# SOM_JB2.net
KiCad netlist of a schematic drawn in Altium Designer
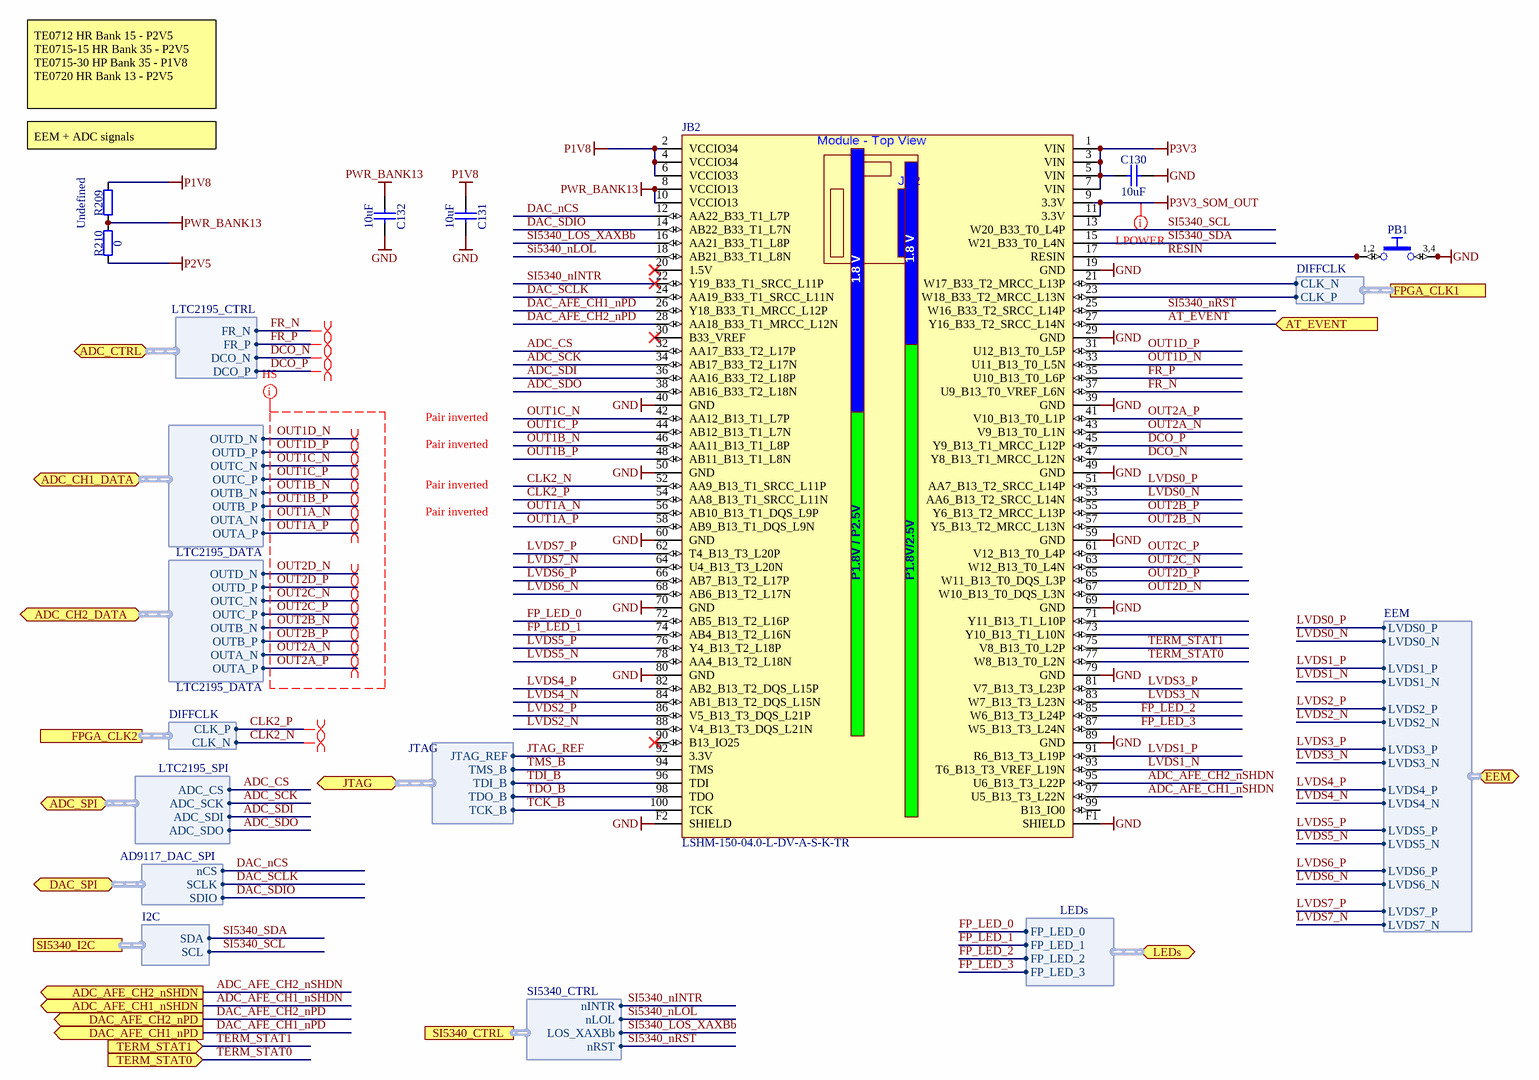
[diagram p0: SOM_JB2.SchDoc]

(export (version "E")
  (design (tool "Eeschema 10.0.6"))
  (components
    (comp (ref "C130")
      (value "10uF")
      (footprint "CAPC1608X80N")
      (description "Non-polarised capacitor")
      (fields
        (field (name "PART NUMBER") "CC0603_10UF_10V_10%_X5R")
        (field (name "VOLTAGE") "10V")
        (field (name "AUTHOR") "CERN DEM JLC")
      )
      (libsource (lib "Capacitors") (part "Capacitor - non polarized"))
    )
    (comp (ref "C131")
      (value "10uF")
      (footprint "CAPC1608X80N")
      (description "Non-polarised capacitor")
      (fields
        (field (name "PART NUMBER") "CC0603_10UF_10V_10%_X5R")
        (field (name "VOLTAGE") "10V")
        (field (name "AUTHOR") "CERN DEM JLC")
      )
      (libsource (lib "Capacitors") (part "Capacitor - non polarized"))
    )
    (comp (ref "C132")
      (value "10uF")
      (footprint "CAPC1608X80N")
      (description "Non-polarised capacitor")
      (fields
        (field (name "PART NUMBER") "CC0603_10UF_10V_10%_X5R")
        (field (name "VOLTAGE") "10V")
        (field (name "AUTHOR") "CERN DEM JLC")
      )
      (libsource (lib "Capacitors") (part "Capacitor - non polarized"))
    )
    (comp (ref "JB2")
      (value "LSHM-150-04.0-L-DV-A-S-K-TR")
      (footprint "LSHM-150-XXX-X-DV-A-X")
      (description "Samtec Razor Beam REF-189017-02, LF-04.0, 60 Pins, für alle 4x5 SoMs")
      (libsource (lib "SVPX_FMC_6U_SOM") (part "25286"))
    )
    (comp (ref "PB1")
      (value "Push Button")
      (footprint "PB_TYCO_FSM6JSMA")
      (description "Push-Button Switch SPDT")
      (fields
        (field (name "PART NUMBER") "PB_TYCO_FSM6JSMA")
        (field (name "MANUFACTURER") "TYCO ELECTRONICS")
        (field (name "AUTHOR") "CERN DEM JLC")
      )
      (libsource (lib "Eletro-mechanical") (part "PB SPST 12NO-34NO"))
    )
    (comp (ref "R209")
      (value "Undefined")
      (footprint "RESC1608X55N")
      (description "Resistor")
      (fields (field (name "PART NUMBER") "R0603_NO-VALUE") (field (name "AUTHOR") "CERN DEM JLC"))
      (libsource (lib "Resistors") (part "Resistor"))
    )
    (comp (ref "R210")
      (value "0")
      (footprint "RESC1005X40N")
      (description "Resistor")
      (fields
        (field (name "PART NUMBER") "R0402_0R_JUMPER")
        (field (name "MANUFACTURER") "GENERIC")
        (field (name "AUTHOR") "CERN DEM JLC")
      )
      (libsource (lib "Resistors") (part "Resistor"))
    )
  )
  (nets
    (net (code "11") (name "/ADC_AFE_CH1_nSHDN") (class "Default")
      (node (ref "JB2") (pin "97") (pinfunction "U5_B13_T3_L22N_97") (pintype "bidirectional"))
    )
    (net (code "12") (name "/ADC_AFE_CH2_nSHDN") (class "Default")
      (node (ref "JB2") (pin "95") (pinfunction "U6_B13_T3_L22P_95") (pintype "bidirectional"))
    )
    (net (code "13") (name "/ADC_CS") (class "Default")
      (node (ref "JB2") (pin "32") (pinfunction "AA17_B33_T2_L17P_32") (pintype "bidirectional"))
    )
    (net (code "14") (name "/ADC_SCK") (class "Default")
      (node (ref "JB2") (pin "34") (pinfunction "AB17_B33_T2_L17N_34") (pintype "bidirectional"))
    )
    (net (code "15") (name "/ADC_SDI") (class "Default")
      (node (ref "JB2") (pin "36") (pinfunction "AA16_B33_T2_L18P_36") (pintype "bidirectional"))
    )
    (net (code "16") (name "/ADC_SDO") (class "Default")
      (node (ref "JB2") (pin "38") (pinfunction "AB16_B33_T2_L18N_38") (pintype "bidirectional"))
    )
    (net (code "17") (name "/AT_EVENT") (class "Default")
      (node (ref "JB2") (pin "27") (pinfunction "Y16_B33_T2_SRCC_L14N_27") (pintype "bidirectional"))
    )
    (net (code "18") (name "/CLK2_N") (class "Default")
      (node (ref "JB2") (pin "52") (pinfunction "AA9_B13_T1_SRCC_L11P_52") (pintype "bidirectional"))
    )
    (net (code "19") (name "/CLK2_P") (class "Default")
      (node (ref "JB2") (pin "54") (pinfunction "AA8_B13_T1_SRCC_L11N_54") (pintype "bidirectional"))
    )
    (net (code "20") (name "/DAC_AFE_CH1_nPD") (class "Default")
      (node (ref "JB2") (pin "26") (pinfunction "Y18_B33_T1_MRCC_L12P_26") (pintype "bidirectional"))
    )
    (net (code "21") (name "/DAC_AFE_CH2_nPD") (class "Default")
      (node (ref "JB2") (pin "28") (pinfunction "AA18_B33_T1_MRCC_L12N_28") (pintype "bidirectional"))
    )
    (net (code "22") (name "/DAC_SCLK") (class "Default")
      (node (ref "JB2") (pin "24") (pinfunction "AA19_B33_T1_SRCC_L11N_24") (pintype "bidirectional"))
    )
    (net (code "23") (name "/DAC_SDIO") (class "Default")
      (node (ref "JB2") (pin "14") (pinfunction "AB22_B33_T1_L7N_14") (pintype "bidirectional"))
    )
    (net (code "24") (name "/DAC_nCS") (class "Default")
      (node (ref "JB2") (pin "12") (pinfunction "AA22_B33_T1_L7P_12") (pintype "bidirectional"))
    )
    (net (code "25") (name "/DCO_N") (class "Default")
      (node (ref "JB2") (pin "47") (pinfunction "Y8_B13_T1_MRCC_L12N_47") (pintype "bidirectional"))
    )
    (net (code "26") (name "/DCO_P") (class "Default")
      (node (ref "JB2") (pin "45") (pinfunction "Y9_B13_T1_MRCC_L12P_45") (pintype "bidirectional"))
    )
    (net (code "27") (name "/FP_LED_0") (class "Default")
      (node (ref "JB2") (pin "72") (pinfunction "AB5_B13_T2_L16P_72") (pintype "bidirectional"))
    )
    (net (code "28") (name "/FP_LED_1") (class "Default")
      (node (ref "JB2") (pin "74") (pinfunction "AB4_B13_T2_L16N_74") (pintype "bidirectional"))
    )
    (net (code "29") (name "/FP_LED_2") (class "Default")
      (node (ref "JB2") (pin "85") (pinfunction "W6_B13_T3_L24P_85") (pintype "bidirectional"))
    )
    (net (code "30") (name "/FP_LED_3") (class "Default")
      (node (ref "JB2") (pin "87") (pinfunction "W5_B13_T3_L24N_87") (pintype "bidirectional"))
    )
    (net (code "31") (name "/FR_N") (class "Default")
      (node (ref "JB2") (pin "37") (pinfunction "U9_B13_T0_VREF_L6N_37") (pintype "bidirectional"))
    )
    (net (code "32") (name "/FR_P") (class "Default")
      (node (ref "JB2") (pin "35") (pinfunction "U10_B13_T0_L6P_35") (pintype "bidirectional"))
    )
    (net (code "33") (name "/JTAG_REF") (class "Default")
      (node (ref "JB2") (pin "92") (pinfunction "3.3V_92") (pintype "power_in"))
    )
    (net (code "34") (name "/LVDS0_N") (class "Default")
      (node (ref "JB2") (pin "53") (pinfunction "AA6_B13_T2_SRCC_L14N_53") (pintype "bidirectional"))
    )
    (net (code "35") (name "/LVDS0_P") (class "Default")
      (node (ref "JB2") (pin "51") (pinfunction "AA7_B13_T2_SRCC_L14P_51") (pintype "bidirectional"))
    )
    (net (code "36") (name "/LVDS1_N") (class "Default")
      (node (ref "JB2") (pin "93") (pinfunction "T6_B13_T3_VREF_L19N_93") (pintype "bidirectional"))
    )
    (net (code "37") (name "/LVDS1_P") (class "Default")
      (node (ref "JB2") (pin "91") (pinfunction "R6_B13_T3_L19P_91") (pintype "bidirectional"))
    )
    (net (code "38") (name "/LVDS2_N") (class "Default")
      (node (ref "JB2") (pin "88") (pinfunction "V4_B13_T3_DQS_L21N_88") (pintype "bidirectional"))
    )
    (net (code "39") (name "/LVDS2_P") (class "Default")
      (node (ref "JB2") (pin "86") (pinfunction "V5_B13_T3_DQS_L21P_86") (pintype "bidirectional"))
    )
    (net (code "40") (name "/LVDS3_N") (class "Default")
      (node (ref "JB2") (pin "83") (pinfunction "W7_B13_T3_L23N_83") (pintype "bidirectional"))
    )
    (net (code "41") (name "/LVDS3_P") (class "Default")
      (node (ref "JB2") (pin "81") (pinfunction "V7_B13_T3_L23P_81") (pintype "bidirectional"))
    )
    (net (code "42") (name "/LVDS4_N") (class "Default")
      (node (ref "JB2") (pin "84") (pinfunction "AB1_B13_T2_DQS_L15N_84") (pintype "bidirectional"))
    )
    (net (code "43") (name "/LVDS4_P") (class "Default")
      (node (ref "JB2") (pin "82") (pinfunction "AB2_B13_T2_DQS_L15P_82") (pintype "bidirectional"))
    )
    (net (code "44") (name "/LVDS5_N") (class "Default")
      (node (ref "JB2") (pin "78") (pinfunction "AA4_B13_T2_L18N_78") (pintype "bidirectional"))
    )
    (net (code "45") (name "/LVDS5_P") (class "Default")
      (node (ref "JB2") (pin "76") (pinfunction "Y4_B13_T2_L18P_76") (pintype "bidirectional"))
    )
    (net (code "46") (name "/LVDS6_N") (class "Default")
      (node (ref "JB2") (pin "68") (pinfunction "AB6_B13_T2_L17N_68") (pintype "bidirectional"))
    )
    (net (code "47") (name "/LVDS6_P") (class "Default")
      (node (ref "JB2") (pin "66") (pinfunction "AB7_B13_T2_L17P_66") (pintype "bidirectional"))
    )
    (net (code "48") (name "/LVDS7_N") (class "Default")
      (node (ref "JB2") (pin "64") (pinfunction "U4_B13_T3_L20N_64") (pintype "bidirectional"))
    )
    (net (code "49") (name "/LVDS7_P") (class "Default")
      (node (ref "JB2") (pin "62") (pinfunction "T4_B13_T3_L20P_62") (pintype "bidirectional"))
    )
    (net (code "50") (name "/OUT1A_N") (class "Default")
      (node (ref "JB2") (pin "56") (pinfunction "AB10_B13_T1_DQS_L9P_56") (pintype "bidirectional"))
    )
    (net (code "51") (name "/OUT1A_P") (class "Default")
      (node (ref "JB2") (pin "58") (pinfunction "AB9_B13_T1_DQS_L9N_58") (pintype "bidirectional"))
    )
    (net (code "52") (name "/OUT1B_N") (class "Default")
      (node (ref "JB2") (pin "46") (pinfunction "AA11_B13_T1_L8P_46") (pintype "bidirectional"))
    )
    (net (code "53") (name "/OUT1B_P") (class "Default")
      (node (ref "JB2") (pin "48") (pinfunction "AB11_B13_T1_L8N_48") (pintype "bidirectional"))
    )
    (net (code "54") (name "/OUT1C_N") (class "Default")
      (node (ref "JB2") (pin "42") (pinfunction "AA12_B13_T1_L7P_42") (pintype "bidirectional"))
    )
    (net (code "55") (name "/OUT1C_P") (class "Default")
      (node (ref "JB2") (pin "44") (pinfunction "AB12_B13_T1_L7N_44") (pintype "bidirectional"))
    )
    (net (code "56") (name "/OUT1D_N") (class "Default")
      (node (ref "JB2") (pin "33") (pinfunction "U11_B13_T0_L5N_33") (pintype "bidirectional"))
    )
    (net (code "57") (name "/OUT1D_P") (class "Default")
      (node (ref "JB2") (pin "31") (pinfunction "U12_B13_T0_L5P_31") (pintype "bidirectional"))
    )
    (net (code "58") (name "/OUT2A_N") (class "Default")
      (node (ref "JB2") (pin "43") (pinfunction "V9_B13_T0_L1N_43") (pintype "bidirectional"))
    )
    (net (code "59") (name "/OUT2A_P") (class "Default")
      (node (ref "JB2") (pin "41") (pinfunction "V10_B13_T0_L1P_41") (pintype "bidirectional"))
    )
    (net (code "60") (name "/OUT2B_N") (class "Default")
      (node (ref "JB2") (pin "57") (pinfunction "Y5_B13_T2_MRCC_L13N_57") (pintype "bidirectional"))
    )
    (net (code "61") (name "/OUT2B_P") (class "Default")
      (node (ref "JB2") (pin "55") (pinfunction "Y6_B13_T2_MRCC_L13P_55") (pintype "bidirectional"))
    )
    (net (code "62") (name "/OUT2C_N") (class "Default")
      (node (ref "JB2") (pin "63") (pinfunction "W12_B13_T0_L4N_63") (pintype "bidirectional"))
    )
    (net (code "63") (name "/OUT2C_P") (class "Default")
      (node (ref "JB2") (pin "61") (pinfunction "V12_B13_T0_L4P_61") (pintype "bidirectional"))
    )
    (net (code "64") (name "/OUT2D_N") (class "Default")
      (node (ref "JB2") (pin "67") (pinfunction "W10_B13_T0_DQS_L3N_67") (pintype "bidirectional"))
    )
    (net (code "65") (name "/OUT2D_P") (class "Default")
      (node (ref "JB2") (pin "65") (pinfunction "W11_B13_T0_DQS_L3P_65") (pintype "bidirectional"))
    )
    (net (code "66") (name "/RESIN") (class "Default")
      (node (ref "JB2") (pin "17") (pinfunction "RESIN_17") (pintype "passive"))
      (node (ref "PB1") (pin "1") (pinfunction "1_1") (pintype "bidirectional"))
      (node (ref "PB1") (pin "2") (pinfunction "2_2") (pintype "bidirectional"))
    )
    (net (code "67") (name "/SI5340_LOS_XAXBb") (class "Default")
      (node (ref "JB2") (pin "16") (pinfunction "AA21_B33_T1_L8P_16") (pintype "bidirectional"))
    )
    (net (code "68") (name "/SI5340_SCL") (class "Default")
      (node (ref "JB2") (pin "13") (pinfunction "W20_B33_T0_L4P_13") (pintype "passive"))
    )
    (net (code "69") (name "/SI5340_SDA") (class "Default")
      (node (ref "JB2") (pin "15") (pinfunction "W21_B33_T0_L4N_15") (pintype "passive"))
    )
    (net (code "70") (name "/SI5340_nINTR") (class "Default")
      (node (ref "JB2") (pin "22") (pinfunction "Y19_B33_T1_SRCC_L11P_22") (pintype "bidirectional+no_connect"))
    )
    (net (code "71") (name "/SI5340_nRST") (class "Default")
      (node (ref "JB2") (pin "25") (pinfunction "W16_B33_T2_SRCC_L14P_25") (pintype "bidirectional"))
    )
    (net (code "72") (name "/Si5340_nLOL") (class "Default")
      (node (ref "JB2") (pin "18") (pinfunction "AB21_B33_T1_L8N_18") (pintype "bidirectional"))
    )
    (net (code "73") (name "/TCK_B") (class "Default")
      (node (ref "JB2") (pin "100") (pinfunction "TCK_100") (pintype "passive"))
    )
    (net (code "74") (name "/TDI_B") (class "Default")
      (node (ref "JB2") (pin "96") (pinfunction "TDI_96") (pintype "passive"))
    )
    (net (code "75") (name "/TDO_B") (class "Default")
      (node (ref "JB2") (pin "98") (pinfunction "TDO_98") (pintype "passive"))
    )
    (net (code "76") (name "/TERM_STAT0") (class "Default")
      (node (ref "JB2") (pin "77") (pinfunction "W8_B13_T0_L2N_77") (pintype "bidirectional"))
    )
    (net (code "77") (name "/TERM_STAT1") (class "Default")
      (node (ref "JB2") (pin "75") (pinfunction "V8_B13_T0_L2P_75") (pintype "bidirectional"))
    )
    (net (code "78") (name "/TMS_B") (class "Default")
      (node (ref "JB2") (pin "94") (pinfunction "TMS_94") (pintype "passive"))
    )
    (net (code "89") (name "GND") (class "Default")
      (node (ref "C130") (pin "2") (pinfunction "2_2") (pintype "passive"))
      (node (ref "C131") (pin "2") (pinfunction "2_2") (pintype "passive"))
      (node (ref "C132") (pin "2") (pinfunction "2_2") (pintype "passive"))
      (node (ref "JB2") (pin "19") (pinfunction "GND_19") (pintype "power_in"))
      (node (ref "JB2") (pin "29") (pinfunction "GND_29") (pintype "power_in"))
      (node (ref "JB2") (pin "39") (pinfunction "GND_39") (pintype "power_in"))
      (node (ref "JB2") (pin "40") (pinfunction "GND_40") (pintype "power_in"))
      (node (ref "JB2") (pin "49") (pinfunction "GND_49") (pintype "power_in"))
      (node (ref "JB2") (pin "50") (pinfunction "GND_50") (pintype "power_in"))
      (node (ref "JB2") (pin "59") (pinfunction "GND_59") (pintype "power_in"))
      (node (ref "JB2") (pin "60") (pinfunction "GND_60") (pintype "power_in"))
      (node (ref "JB2") (pin "69") (pinfunction "GND_69") (pintype "power_in"))
      (node (ref "JB2") (pin "70") (pinfunction "GND_70") (pintype "power_in"))
      (node (ref "JB2") (pin "79") (pinfunction "GND_79") (pintype "power_in"))
      (node (ref "JB2") (pin "80") (pinfunction "GND_80") (pintype "power_in"))
      (node (ref "JB2") (pin "89") (pinfunction "GND_89") (pintype "power_in"))
      (node (ref "JB2") (pin "F1") (pinfunction "SHIELD_F1") (pintype "power_in"))
      (node (ref "JB2") (pin "F2") (pinfunction "SHIELD_F2") (pintype "power_in"))
      (node (ref "PB1") (pin "3") (pinfunction "3_3") (pintype "bidirectional"))
      (node (ref "PB1") (pin "4") (pinfunction "4_4") (pintype "bidirectional"))
    )
    (net (code "90") (name "P1V8") (class "Default")
      (node (ref "C131") (pin "1") (pinfunction "1_1") (pintype "passive"))
      (node (ref "JB2") (pin "2") (pinfunction "VCCIO34_2") (pintype "power_in"))
      (node (ref "JB2") (pin "4") (pinfunction "VCCIO34_4") (pintype "power_in"))
      (node (ref "JB2") (pin "6") (pinfunction "VCCIO33_6") (pintype "power_in"))
      (node (ref "R209") (pin "2") (pinfunction "2_2") (pintype "passive"))
    )
    (net (code "91") (name "P2V5") (class "Default")
      (node (ref "R210") (pin "1") (pinfunction "1_1") (pintype "passive"))
    )
    (net (code "92") (name "P3V3") (class "Default")
      (node (ref "C130") (pin "1") (pinfunction "1_1") (pintype "passive"))
      (node (ref "JB2") (pin "1") (pinfunction "VIN_1") (pintype "power_in"))
      (node (ref "JB2") (pin "3") (pinfunction "VIN_3") (pintype "power_in"))
      (node (ref "JB2") (pin "5") (pinfunction "VIN_5") (pintype "power_in"))
      (node (ref "JB2") (pin "7") (pinfunction "VIN_7") (pintype "power_in"))
    )
    (net (code "93") (name "P3V3_SOM_OUT") (class "Default")
      (node (ref "JB2") (pin "11") (pinfunction "3.3V_11") (pintype "power_in"))
      (node (ref "JB2") (pin "9") (pinfunction "3.3V_9") (pintype "power_in"))
    )
    (net (code "94") (name "PWR_BANK13") (class "Default")
      (node (ref "C132") (pin "1") (pinfunction "1_1") (pintype "passive"))
      (node (ref "JB2") (pin "10") (pinfunction "VCCIO13_10") (pintype "power_in"))
      (node (ref "JB2") (pin "8") (pinfunction "VCCIO13_8") (pintype "power_in"))
      (node (ref "R209") (pin "1") (pinfunction "1_1") (pintype "passive"))
      (node (ref "R210") (pin "2") (pinfunction "2_2") (pintype "passive"))
    )
    (net (code "95") (name "unconnected-(JB2-1.5V-Pad20)") (class "Default")
      (node (ref "JB2") (pin "20") (pinfunction "1.5V_20") (pintype "power_in+no_connect"))
    )
    (net (code "96") (name "unconnected-(JB2-B13_IO0-Pad99)") (class "Default")
      (node (ref "JB2") (pin "99") (pinfunction "B13_IO0_99") (pintype "bidirectional"))
    )
    (net (code "97") (name "unconnected-(JB2-B13_IO25-Pad90)") (class "Default")
      (node (ref "JB2") (pin "90") (pinfunction "B13_IO25_90") (pintype "bidirectional+no_connect"))
    )
    (net (code "98") (name "unconnected-(JB2-B33_VREF-Pad30)") (class "Default")
      (node (ref "JB2") (pin "30") (pinfunction "B33_VREF_30") (pintype "power_in+no_connect"))
    )
    (net (code "99") (name "unconnected-(JB2-W17_B33_T2_MRCC_L13P-Pad21)") (class "Default")
      (node (ref "JB2") (pin "21") (pinfunction "W17_B33_T2_MRCC_L13P_21") (pintype "bidirectional"))
    )
    (net (code "100") (name "unconnected-(JB2-W18_B33_T2_MRCC_L13N-Pad23)") (class "Default")
      (node (ref "JB2") (pin "23") (pinfunction "W18_B33_T2_MRCC_L13N_23") (pintype "bidirectional"))
    )
    (net (code "101") (name "unconnected-(JB2-Y10_B13_T1_L10N-Pad73)") (class "Default")
      (node (ref "JB2") (pin "73") (pinfunction "Y10_B13_T1_L10N_73") (pintype "bidirectional"))
    )
    (net (code "102") (name "unconnected-(JB2-Y11_B13_T1_L10P-Pad71)") (class "Default")
      (node (ref "JB2") (pin "71") (pinfunction "Y11_B13_T1_L10P_71") (pintype "bidirectional"))
    )
  )
)
